# NG2093_IMU.net
KiCad netlist of a schematic drawn in Altium Designer
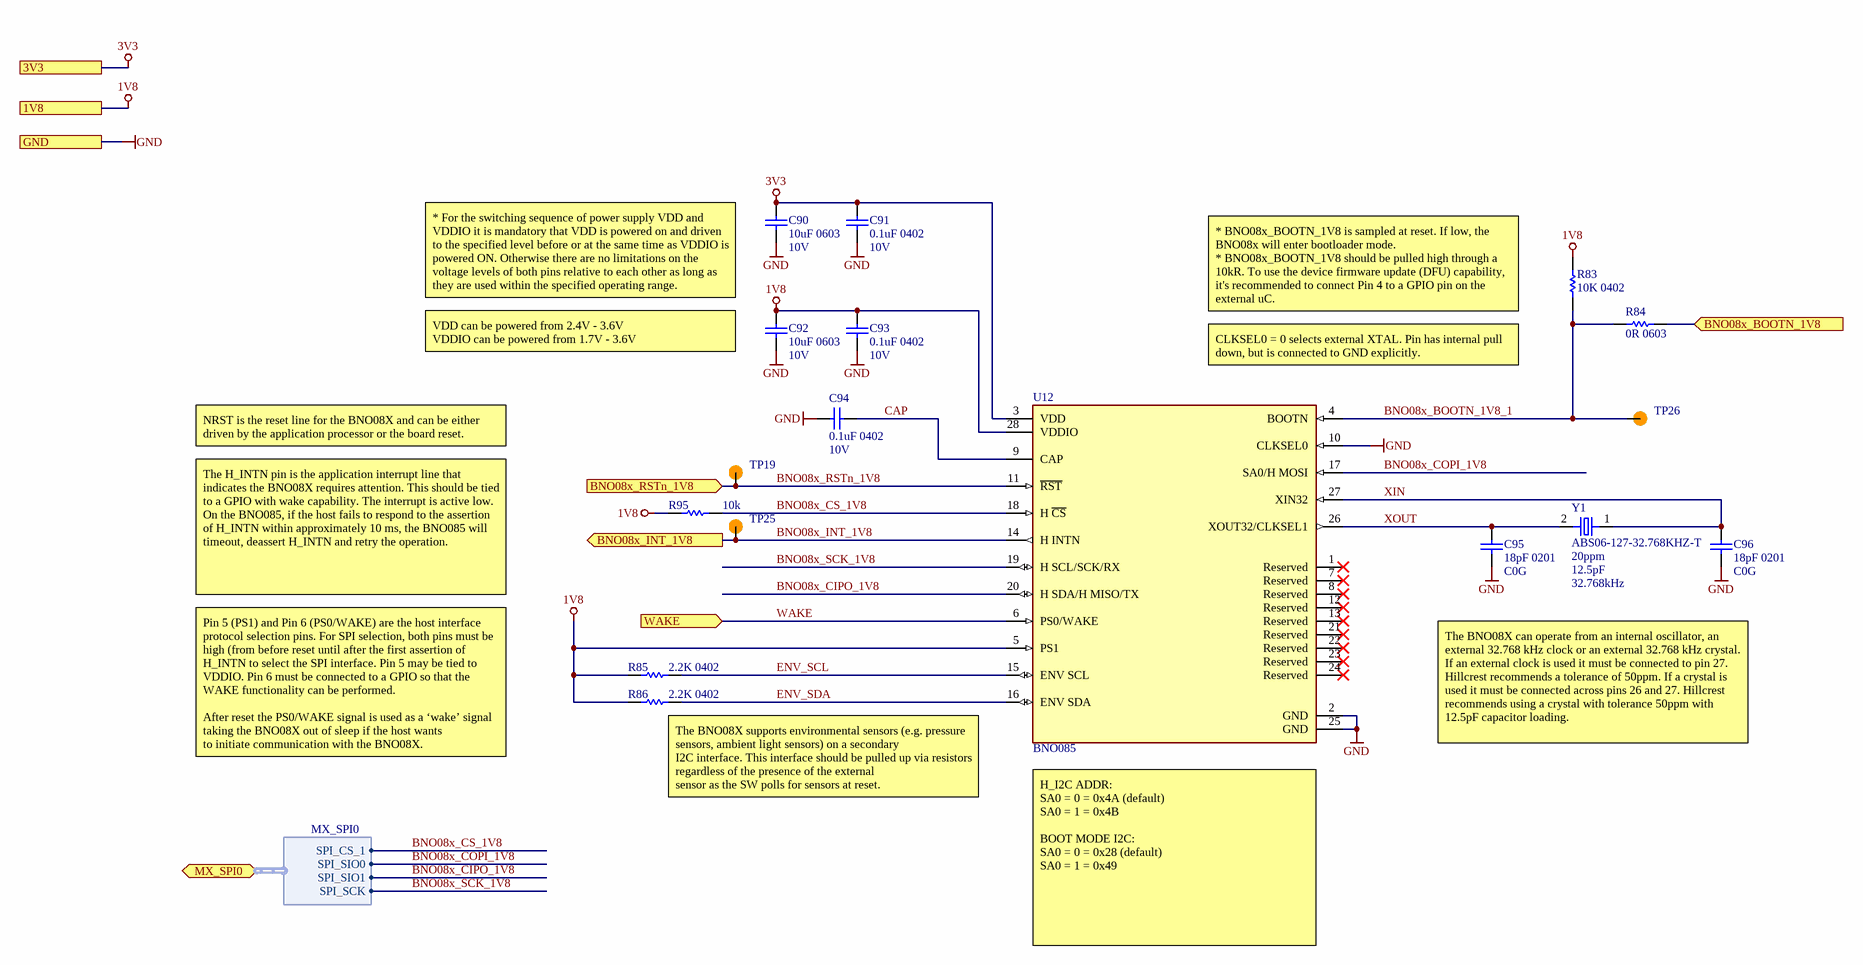
[diagram p0: NG2093_IMU.SchDoc]

(export (version "E")
  (design (tool "Eeschema 10.0.6"))
  (components
    (comp (ref "C90")
      (value "10uF 0603")
      (footprint "CAP_Altium_Vault_Generic:CAPC0603(1608)100_L")
      (description "CAP CER 10UF 10V X5R 0603 20%")
      (fields (field (name "TOLERANCE") "20%") (field (name "VOLTAGE RATING") "10V"))
      (libsource (lib "LuxonisMaster") (part "GRM188R61A106ME69D"))
    )
    (comp (ref "C91")
      (value "0.1uF 0402")
      (footprint "CAP_Altium_Vault_Generic:CAPC0402(1005)70_L")
      (description "CAP CER 0.1UF 10V X7R 0402 5%")
      (fields (field (name "TOLERANCE") "5%") (field (name "VOLTAGE RATING") "10V"))
      (libsource (lib "LuxonisMaster") (part "GRM155R71A104JA01D"))
    )
    (comp (ref "C92")
      (value "10uF 0603")
      (footprint "CAP_Altium_Vault_Generic:CAPC0603(1608)100_L")
      (description "CAP CER 10UF 10V X5R 0603 20%")
      (fields (field (name "TOLERANCE") "20%") (field (name "VOLTAGE RATING") "10V"))
      (libsource (lib "LuxonisMaster") (part "GRM188R61A106ME69D"))
    )
    (comp (ref "C93")
      (value "0.1uF 0402")
      (footprint "CAP_Altium_Vault_Generic:CAPC0402(1005)70_L")
      (description "CAP CER 0.1UF 10V X7R 0402 5%")
      (fields (field (name "TOLERANCE") "5%") (field (name "VOLTAGE RATING") "10V"))
      (libsource (lib "LuxonisMaster") (part "GRM155R71A104JA01D"))
    )
    (comp (ref "C94")
      (value "0.1uF 0402")
      (footprint "CAP_Altium_Vault_Generic:CAPC0402(1005)70_L")
      (description "CAP CER 0.1UF 10V X7R 0402 5%")
      (fields (field (name "TOLERANCE") "5%") (field (name "VOLTAGE RATING") "10V"))
      (libsource (lib "LuxonisMaster") (part "GRM155R71A104JA01D"))
    )
    (comp (ref "C95")
      (value "18pF 0201")
      (footprint "CAP_Altium_Vault_Generic:CAPC0201(0603)33_L")
      (description "Cap Ceramic 18pF 25V C0G 1% Pad SMD 0201 125C T/R")
      (fields (field (name "TOLERANCE") "1%") (field (name "DIELECTRIC") "C0G"))
      (libsource (lib "BW1092_R0M0E0") (part "GRM0335C1E180FA01D"))
    )
    (comp (ref "C96")
      (value "18pF 0201")
      (footprint "CAP_Altium_Vault_Generic:CAPC0201(0603)33_L")
      (description "Cap Ceramic 18pF 25V C0G 1% Pad SMD 0201 125C T/R")
      (fields (field (name "TOLERANCE") "1%") (field (name "DIELECTRIC") "C0G"))
      (libsource (lib "BW1092_R0M0E0") (part "GRM0335C1E180FA01D"))
    )
    (comp (ref "R83")
      (value "10K 0402")
      (footprint "RES_Altium_Vault_Generic:RESC0402(1005)_L")
      (fields (field (name "TOLERANCE") "1%"))
      (libsource (lib "LuxonisMaster") (part "RC0402FR-1310KL"))
    )
    (comp (ref "R84")
      (value "0R 0603")
      (footprint "RES_Altium_Vault_Generic:RESC0603(1608)_L")
      (fields (field (name "TOLERANCE") "5%"))
      (libsource (lib "LuxonisMaster") (part "CRCW06030000Z0EA"))
    )
    (comp (ref "R85")
      (value "2.2K 0402")
      (footprint "RES_Altium_Vault_Generic:RESC0402(1005)_L")
      (description "RES SMD 2.2K OHM 1% 1/16W 0402")
      (fields (field (name "TOLERANCE") "1%"))
      (libsource (lib "LuxonisMaster") (part "RC0402FR-072K2L"))
    )
    (comp (ref "R86")
      (value "2.2K 0402")
      (footprint "RES_Altium_Vault_Generic:RESC0402(1005)_L")
      (description "RES SMD 2.2K OHM 1% 1/16W 0402")
      (fields (field (name "TOLERANCE") "1%"))
      (libsource (lib "LuxonisMaster") (part "RC0402FR-072K2L"))
    )
    (comp (ref "R95")
      (value "10k")
      (footprint "RESC0402(1005)_L")
      (description "RES SMD 10K OHM 1% 1/16W 0402")
      (fields (field (name "TOLERANCE") "1%") (field (name "Comment") "RC0402FR-1310KL"))
      (libsource (lib "Luxonis LLC") (part "RC0402FR-0722RL_1"))
    )
    (comp (ref "TP19")
      (value "TP100_200_NS")
      (footprint "TP100_200_NS")
      (libsource (lib "LuxonisMaster") (part "TEST_POINT"))
    )
    (comp (ref "TP25")
      (value "TP100_200_NS")
      (footprint "TP100_200_NS")
      (libsource (lib "LuxonisMaster") (part "TEST_POINT"))
    )
    (comp (ref "TP26")
      (value "TP100_200_NS")
      (footprint "TP100_200_NS")
      (libsource (lib "LuxonisMaster") (part "TEST_POINT"))
    )
    (comp (ref "U12")
      (value "BNO085")
      (footprint "BW1092_R0M0E0:BNO085")
      (description "IMU ACCEL/GYRO/MAG I2C 32BIT")
      (libsource (lib "BW1092_R0M0E0") (part "BNO085"))
    )
    (comp (ref "Y1")
      (value "ABS06-127-32.768KHZ-T")
      (footprint "BW1092_R0M0E0:ABS06-127-32.768KHZ-T")
      (description "CRYSTAL 32.768kHz ±20ppm Crystal 12.5pF 90 kOhms 2-SMD, No Lead")
      (fields
        (field (name "FREQUENCY TOLERANCE") "20ppm")
        (field (name "LOAD CAPACITANCE") "12.5pF")
        (field (name "FREQUENCY") "32.768kHz")
      )
      (libsource (lib "BW1092_R0M0E0") (part "ABS06-127-32.768KHZ-T"))
    )
  )
  (nets
    (net (code "2") (name "/BNO08x_BOOTN_1V8") (class "Default")
      (node (ref "R84") (pin "2") (pinfunction "2_2") (pintype "passive"))
    )
    (net (code "3") (name "/BNO08x_BOOTN_1V8_1") (class "Default")
      (node (ref "R83") (pin "1") (pinfunction "1_1") (pintype "passive"))
      (node (ref "R84") (pin "1") (pinfunction "1_1") (pintype "passive"))
      (node (ref "TP26") (pin "1") (pintype "passive"))
      (node (ref "U12") (pin "4") (pinfunction "BOOTN_4") (pintype "input"))
    )
    (net (code "4") (name "/BNO08x_CIPO_1V8") (class "Default")
      (node (ref "U12") (pin "20") (pinfunction "H_SDA/H_MISO/TX_20") (pintype "bidirectional"))
    )
    (net (code "5") (name "/BNO08x_COPI_1V8") (class "Default")
      (node (ref "U12") (pin "17") (pinfunction "SA0/H_MOSI_17") (pintype "input"))
    )
    (net (code "6") (name "/BNO08x_CS_1V8") (class "Default")
      (node (ref "R95") (pin "2") (pinfunction "2_2") (pintype "passive"))
      (node (ref "U12") (pin "18") (pinfunction "H_~{CS}_18") (pintype "input"))
    )
    (net (code "7") (name "/BNO08x_INT_1V8") (class "Default")
      (node (ref "TP25") (pin "1") (pintype "passive"))
      (node (ref "U12") (pin "14") (pinfunction "H_INTN_14") (pintype "output"))
    )
    (net (code "8") (name "/BNO08x_RSTn_1V8") (class "Default")
      (node (ref "TP19") (pin "1") (pintype "passive"))
      (node (ref "U12") (pin "11") (pinfunction "~{RST}_11") (pintype "input"))
    )
    (net (code "9") (name "/BNO08x_SCK_1V8") (class "Default")
      (node (ref "U12") (pin "19") (pinfunction "H_SCL/SCK/RX_19") (pintype "bidirectional"))
    )
    (net (code "10") (name "/CAP") (class "Default")
      (node (ref "C94") (pin "1") (pinfunction "1_1") (pintype "passive"))
      (node (ref "U12") (pin "9") (pinfunction "CAP_9") (pintype "passive"))
    )
    (net (code "11") (name "/ENV_SCL") (class "Default")
      (node (ref "R85") (pin "2") (pinfunction "2_2") (pintype "passive"))
      (node (ref "U12") (pin "15") (pinfunction "ENV_SCL_15") (pintype "bidirectional"))
    )
    (net (code "12") (name "/ENV_SDA") (class "Default")
      (node (ref "R86") (pin "2") (pinfunction "2_2") (pintype "passive"))
      (node (ref "U12") (pin "16") (pinfunction "ENV_SDA_16") (pintype "bidirectional"))
    )
    (net (code "13") (name "/WAKE") (class "Default")
      (node (ref "U12") (pin "6") (pinfunction "PS0/WAKE_6") (pintype "input"))
    )
    (net (code "14") (name "/XIN") (class "Default")
      (node (ref "C96") (pin "2") (pinfunction "2_2") (pintype "passive"))
      (node (ref "U12") (pin "27") (pinfunction "XIN32_27") (pintype "input"))
      (node (ref "Y1") (pin "1") (pinfunction "1_1") (pintype "passive"))
    )
    (net (code "15") (name "/XOUT") (class "Default")
      (node (ref "C95") (pin "2") (pinfunction "2_2") (pintype "passive"))
      (node (ref "U12") (pin "26") (pinfunction "XOUT32/CLKSEL1_26") (pintype "output"))
      (node (ref "Y1") (pin "2") (pinfunction "2_2") (pintype "passive"))
    )
    (net (code "17") (name "1V8") (class "Default")
      (node (ref "C92") (pin "2") (pinfunction "2_2") (pintype "passive"))
      (node (ref "C93") (pin "2") (pinfunction "2_2") (pintype "passive"))
      (node (ref "R83") (pin "2") (pinfunction "2_2") (pintype "passive"))
      (node (ref "R85") (pin "1") (pinfunction "1_1") (pintype "passive"))
      (node (ref "R86") (pin "1") (pinfunction "1_1") (pintype "passive"))
      (node (ref "R95") (pin "1") (pinfunction "1_1") (pintype "passive"))
      (node (ref "U12") (pin "28") (pinfunction "VDDIO_28") (pintype "power_in"))
      (node (ref "U12") (pin "5") (pinfunction "PS1_5") (pintype "input"))
    )
    (net (code "18") (name "3V3") (class "Default")
      (node (ref "C90") (pin "2") (pinfunction "2_2") (pintype "passive"))
      (node (ref "C91") (pin "2") (pinfunction "2_2") (pintype "passive"))
      (node (ref "U12") (pin "3") (pinfunction "VDD_3") (pintype "power_in"))
    )
    (net (code "19") (name "GND") (class "Default")
      (node (ref "C90") (pin "1") (pinfunction "1_1") (pintype "passive"))
      (node (ref "C91") (pin "1") (pinfunction "1_1") (pintype "passive"))
      (node (ref "C92") (pin "1") (pinfunction "1_1") (pintype "passive"))
      (node (ref "C93") (pin "1") (pinfunction "1_1") (pintype "passive"))
      (node (ref "C94") (pin "2") (pinfunction "2_2") (pintype "passive"))
      (node (ref "C95") (pin "1") (pinfunction "1_1") (pintype "passive"))
      (node (ref "C96") (pin "1") (pinfunction "1_1") (pintype "passive"))
      (node (ref "U12") (pin "10") (pinfunction "CLKSEL0_10") (pintype "input"))
      (node (ref "U12") (pin "2") (pinfunction "GND_2") (pintype "power_in"))
      (node (ref "U12") (pin "25") (pinfunction "GND_25") (pintype "power_in"))
    )
    (net (code "20") (name "unconnected-(U12-Reserved-Pad1)") (class "Default")
      (node (ref "U12") (pin "1") (pinfunction "Reserved_1") (pintype "passive+no_connect"))
    )
    (net (code "21") (name "unconnected-(U12-Reserved-Pad7)") (class "Default")
      (node (ref "U12") (pin "7") (pinfunction "Reserved_7") (pintype "passive+no_connect"))
    )
    (net (code "22") (name "unconnected-(U12-Reserved-Pad8)") (class "Default")
      (node (ref "U12") (pin "8") (pinfunction "Reserved_8") (pintype "passive+no_connect"))
    )
    (net (code "23") (name "unconnected-(U12-Reserved-Pad12)") (class "Default")
      (node (ref "U12") (pin "12") (pinfunction "Reserved_12") (pintype "passive+no_connect"))
    )
    (net (code "24") (name "unconnected-(U12-Reserved-Pad13)") (class "Default")
      (node (ref "U12") (pin "13") (pinfunction "Reserved_13") (pintype "passive+no_connect"))
    )
    (net (code "25") (name "unconnected-(U12-Reserved-Pad21)") (class "Default")
      (node (ref "U12") (pin "21") (pinfunction "Reserved_21") (pintype "passive+no_connect"))
    )
    (net (code "26") (name "unconnected-(U12-Reserved-Pad22)") (class "Default")
      (node (ref "U12") (pin "22") (pinfunction "Reserved_22") (pintype "passive+no_connect"))
    )
    (net (code "27") (name "unconnected-(U12-Reserved-Pad23)") (class "Default")
      (node (ref "U12") (pin "23") (pinfunction "Reserved_23") (pintype "passive+no_connect"))
    )
    (net (code "28") (name "unconnected-(U12-Reserved-Pad24)") (class "Default")
      (node (ref "U12") (pin "24") (pinfunction "Reserved_24") (pintype "passive+no_connect"))
    )
  )
)
